# le_grand_strum_stencil.net
KiCad netlist of a schematic drawn in EAGLE
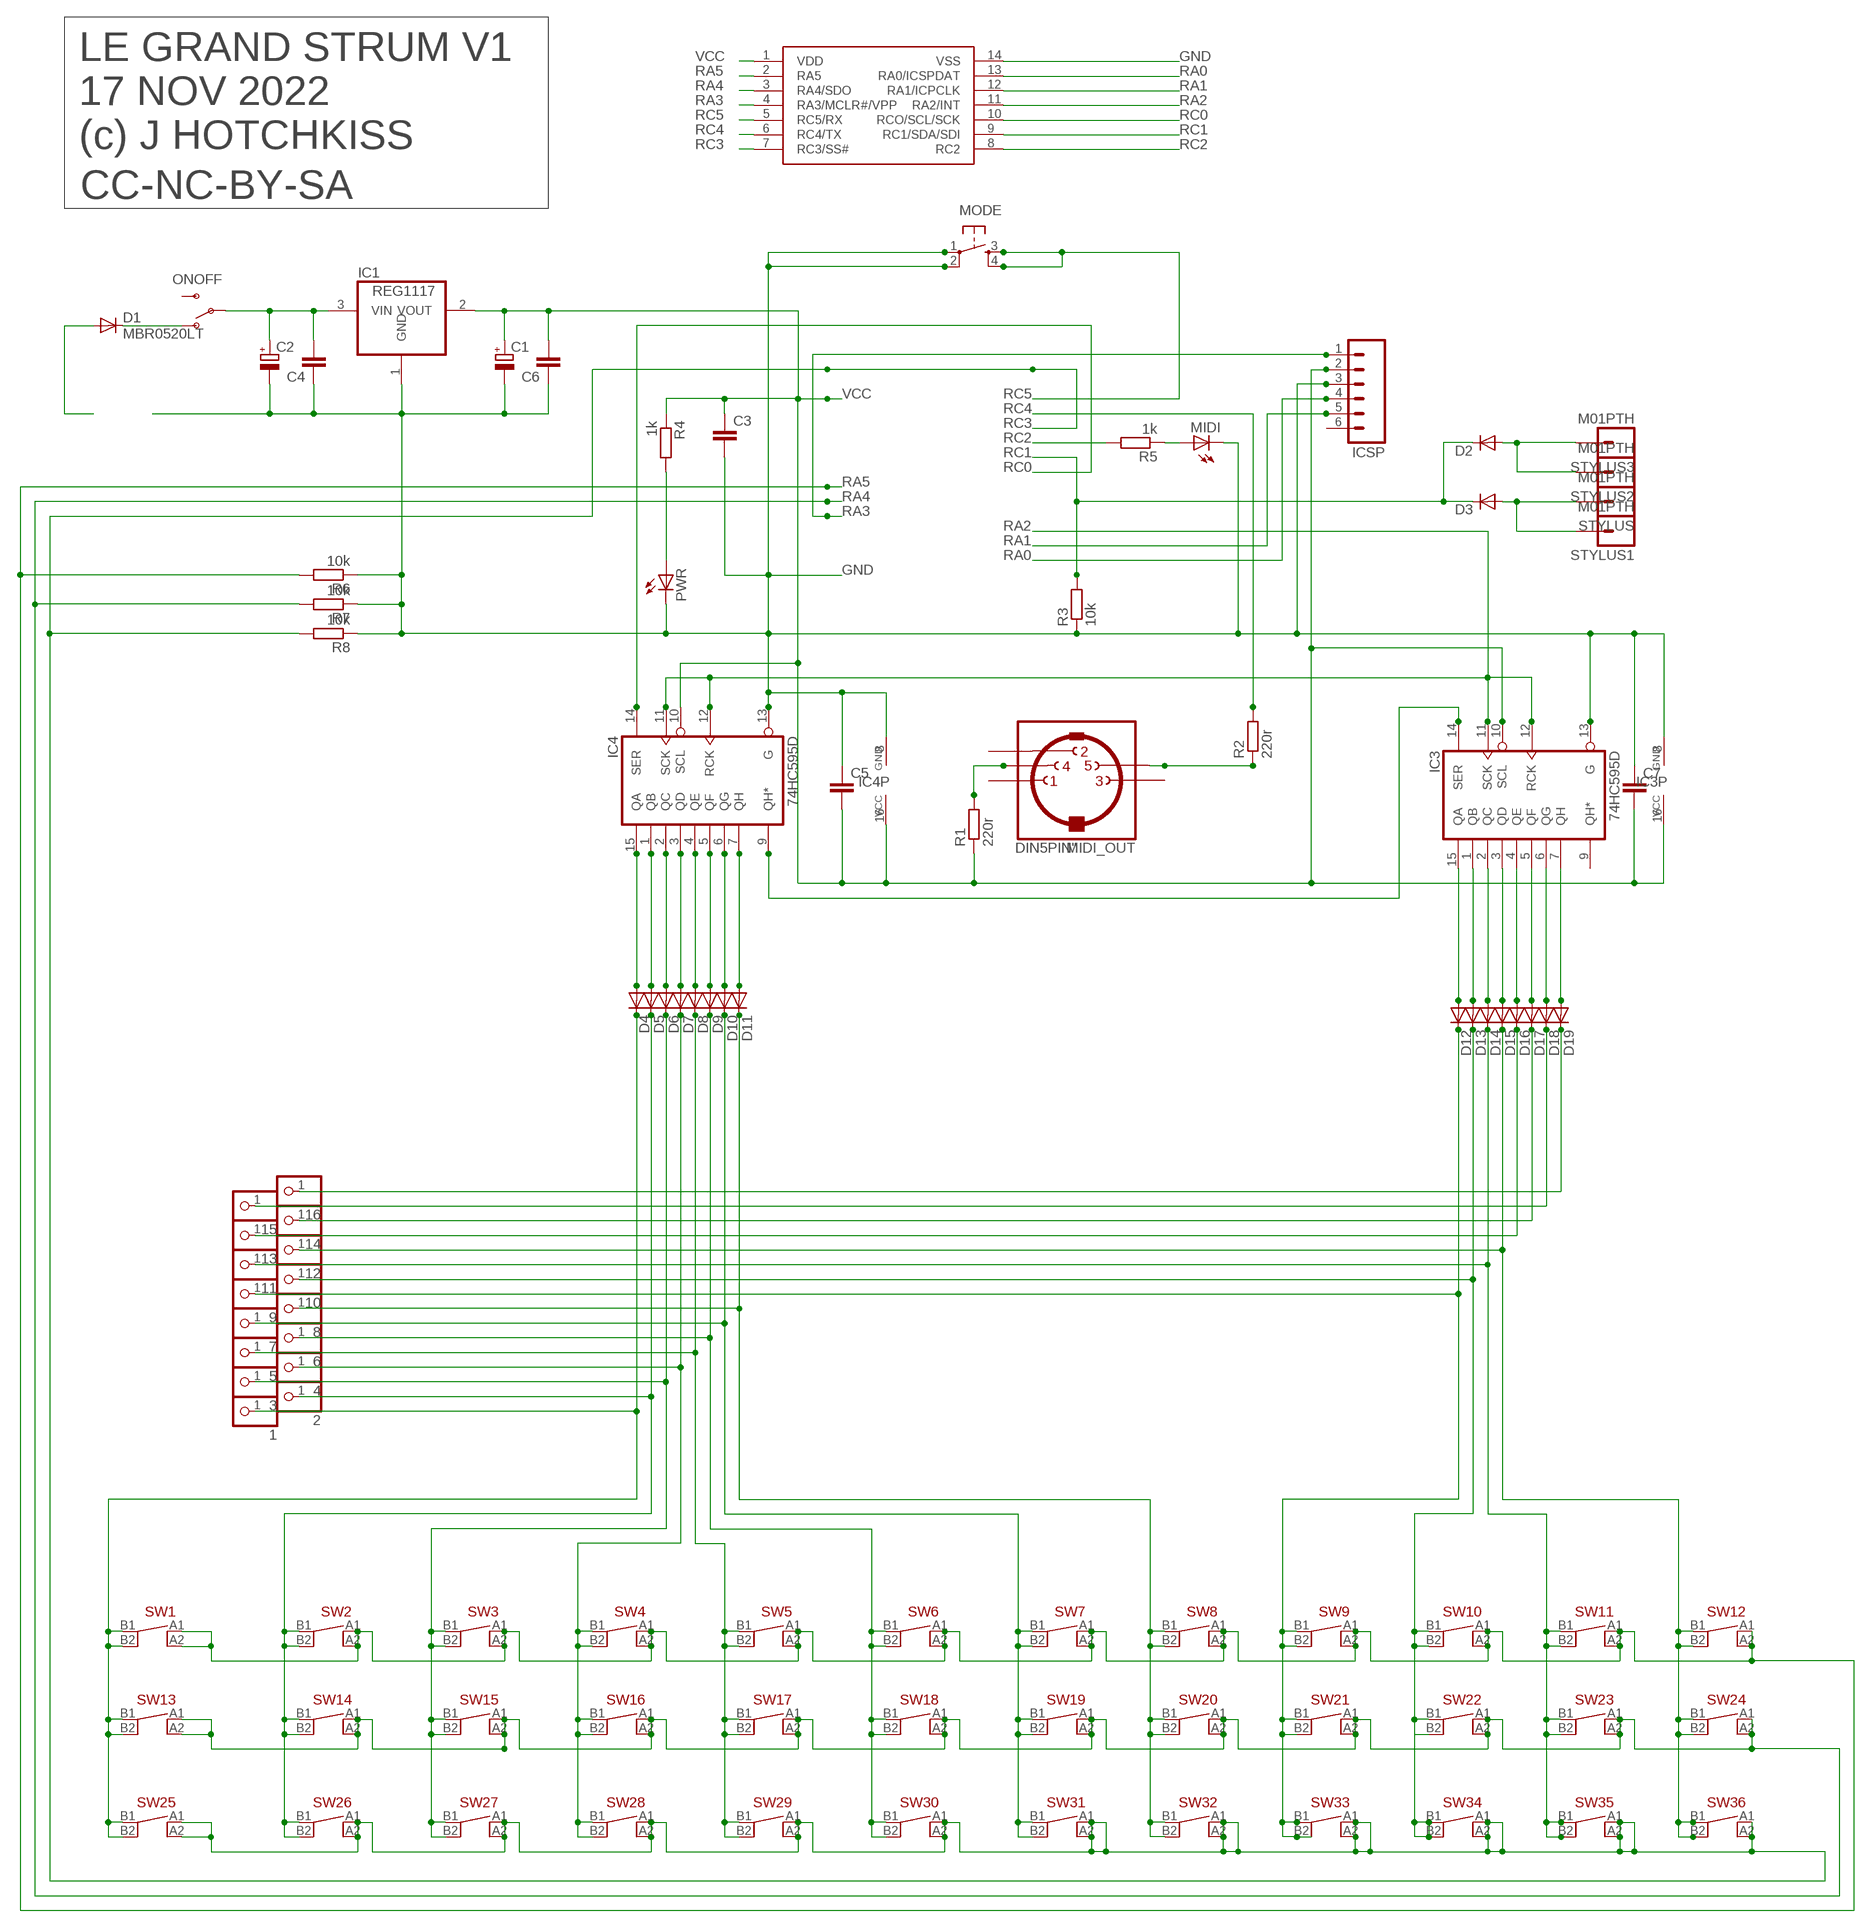
[diagram p0: schematic, sheet 1]

(export (version "E")
  (design (tool "Eeschema 10.0.6"))
  (components
    (comp (ref "1")
      (value "PINHD-1X1")
      (footprint "eagle-import:1X01")
      (libsource (lib "eagle-import") (part "PINHD-1X1"))
    )
    (comp (ref "2")
      (value "PINHD-1X1")
      (footprint "eagle-import:1X01")
      (libsource (lib "eagle-import") (part "PINHD-1X1"))
    )
    (comp (ref "3")
      (value "PINHD-1X1")
      (footprint "eagle-import:1X01")
      (libsource (lib "eagle-import") (part "PINHD-1X1"))
    )
    (comp (ref "4")
      (value "PINHD-1X1")
      (footprint "eagle-import:1X01")
      (libsource (lib "eagle-import") (part "PINHD-1X1"))
    )
    (comp (ref "5")
      (value "PINHD-1X1")
      (footprint "eagle-import:1X01")
      (libsource (lib "eagle-import") (part "PINHD-1X1"))
    )
    (comp (ref "6")
      (value "PINHD-1X1")
      (footprint "eagle-import:1X01")
      (libsource (lib "eagle-import") (part "PINHD-1X1"))
    )
    (comp (ref "7")
      (value "PINHD-1X1")
      (footprint "eagle-import:1X01")
      (libsource (lib "eagle-import") (part "PINHD-1X1"))
    )
    (comp (ref "8")
      (value "PINHD-1X1")
      (footprint "eagle-import:1X01")
      (libsource (lib "eagle-import") (part "PINHD-1X1"))
    )
    (comp (ref "9")
      (value "PINHD-1X1")
      (footprint "eagle-import:1X01")
      (libsource (lib "eagle-import") (part "PINHD-1X1"))
    )
    (comp (ref "10")
      (value "PINHD-1X1")
      (footprint "eagle-import:1X01")
      (libsource (lib "eagle-import") (part "PINHD-1X1"))
    )
    (comp (ref "11")
      (value "PINHD-1X1")
      (footprint "eagle-import:1X01")
      (libsource (lib "eagle-import") (part "PINHD-1X1"))
    )
    (comp (ref "12")
      (value "PINHD-1X1")
      (footprint "eagle-import:1X01")
      (libsource (lib "eagle-import") (part "PINHD-1X1"))
    )
    (comp (ref "13")
      (value "PINHD-1X1")
      (footprint "eagle-import:1X01")
      (libsource (lib "eagle-import") (part "PINHD-1X1"))
    )
    (comp (ref "14")
      (value "PINHD-1X1")
      (footprint "eagle-import:1X01")
      (libsource (lib "eagle-import") (part "PINHD-1X1"))
    )
    (comp (ref "15")
      (value "PINHD-1X1")
      (footprint "eagle-import:1X01")
      (libsource (lib "eagle-import") (part "PINHD-1X1"))
    )
    (comp (ref "16")
      (value "PINHD-1X1")
      (footprint "eagle-import:1X01")
      (libsource (lib "eagle-import") (part "PINHD-1X1"))
    )
    (comp (ref "C1")
      (value "CPOL-EUE2-5")
      (footprint "eagle-import:E2-5")
      (libsource (lib "eagle-import") (part "CPOL-EUE2-5"))
    )
    (comp (ref "C2")
      (value "CPOL-EUE2-5")
      (footprint "eagle-import:E2-5")
      (libsource (lib "eagle-import") (part "CPOL-EUE2-5"))
    )
    (comp (ref "C3")
      (value "C-EUC0805")
      (footprint "eagle-import:C0805")
      (libsource (lib "eagle-import") (part "C-EUC0805"))
    )
    (comp (ref "C4")
      (value "C-EUC0805")
      (footprint "eagle-import:C0805")
      (libsource (lib "eagle-import") (part "C-EUC0805"))
    )
    (comp (ref "C5")
      (value "C-EUC0805")
      (footprint "eagle-import:C0805")
      (libsource (lib "eagle-import") (part "C-EUC0805"))
    )
    (comp (ref "C6")
      (value "C-EUC0805")
      (footprint "eagle-import:C0805")
      (libsource (lib "eagle-import") (part "C-EUC0805"))
    )
    (comp (ref "C7")
      (value "C-EUC0805")
      (footprint "eagle-import:C0805")
      (libsource (lib "eagle-import") (part "C-EUC0805"))
    )
    (comp (ref "D1")
      (value "MBR0520LT")
      (footprint "eagle-import:SOD123")
      (libsource (lib "eagle-import") (part "MBR0520LT"))
    )
    (comp (ref "D2")
      (value "TS4148")
      (footprint "eagle-import:D0805")
      (libsource (lib "eagle-import") (part "TS4148"))
    )
    (comp (ref "D3")
      (value "TS4148")
      (footprint "eagle-import:D0805")
      (libsource (lib "eagle-import") (part "TS4148"))
    )
    (comp (ref "D4")
      (value "TS4148")
      (footprint "eagle-import:D0805")
      (libsource (lib "eagle-import") (part "TS4148"))
    )
    (comp (ref "D5")
      (value "TS4148")
      (footprint "eagle-import:D0805")
      (libsource (lib "eagle-import") (part "TS4148"))
    )
    (comp (ref "D6")
      (value "TS4148")
      (footprint "eagle-import:D0805")
      (libsource (lib "eagle-import") (part "TS4148"))
    )
    (comp (ref "D7")
      (value "TS4148")
      (footprint "eagle-import:D0805")
      (libsource (lib "eagle-import") (part "TS4148"))
    )
    (comp (ref "D8")
      (value "TS4148")
      (footprint "eagle-import:D0805")
      (libsource (lib "eagle-import") (part "TS4148"))
    )
    (comp (ref "D9")
      (value "TS4148")
      (footprint "eagle-import:D0805")
      (libsource (lib "eagle-import") (part "TS4148"))
    )
    (comp (ref "D10")
      (value "TS4148")
      (footprint "eagle-import:D0805")
      (libsource (lib "eagle-import") (part "TS4148"))
    )
    (comp (ref "D11")
      (value "TS4148")
      (footprint "eagle-import:D0805")
      (libsource (lib "eagle-import") (part "TS4148"))
    )
    (comp (ref "D12")
      (value "TS4148")
      (footprint "eagle-import:D0805")
      (libsource (lib "eagle-import") (part "TS4148"))
    )
    (comp (ref "D13")
      (value "TS4148")
      (footprint "eagle-import:D0805")
      (libsource (lib "eagle-import") (part "TS4148"))
    )
    (comp (ref "D14")
      (value "TS4148")
      (footprint "eagle-import:D0805")
      (libsource (lib "eagle-import") (part "TS4148"))
    )
    (comp (ref "D15")
      (value "TS4148")
      (footprint "eagle-import:D0805")
      (libsource (lib "eagle-import") (part "TS4148"))
    )
    (comp (ref "D16")
      (value "TS4148")
      (footprint "eagle-import:D0805")
      (libsource (lib "eagle-import") (part "TS4148"))
    )
    (comp (ref "D17")
      (value "TS4148")
      (footprint "eagle-import:D0805")
      (libsource (lib "eagle-import") (part "TS4148"))
    )
    (comp (ref "D18")
      (value "TS4148")
      (footprint "eagle-import:D0805")
      (libsource (lib "eagle-import") (part "TS4148"))
    )
    (comp (ref "D19")
      (value "TS4148")
      (footprint "eagle-import:D0805")
      (libsource (lib "eagle-import") (part "TS4148"))
    )
    (comp (ref "IC1")
      (value "REG1117")
      (footprint "eagle-import:SOT223")
      (libsource (lib "eagle-import") (part "REG1117"))
    )
    (comp (ref "IC2")
      (value "PIC16F1825SO14")
      (footprint "eagle-import:SO14")
      (libsource (lib "eagle-import") (part "PIC16F1825SO14"))
    )
    (comp (ref "IC3")
      (value "74HC595D")
      (footprint "eagle-import:SO16")
      (libsource (lib "eagle-import") (part "74595DHC"))
    )
    (comp (ref "IC4")
      (value "74HC595D")
      (footprint "eagle-import:SO16")
      (libsource (lib "eagle-import") (part "74595DHC"))
    )
    (comp (ref "ICSP")
      (value "M06SIP")
      (footprint "eagle-import:1X06")
      (libsource (lib "eagle-import") (part "M06SIP"))
    )
    (comp (ref "MIDI")
      (value "LEDCHIPLED_0805")
      (footprint "eagle-import:CHIPLED_0805")
      (libsource (lib "eagle-import") (part "LEDCHIPLED_0805"))
    )
    (comp (ref "MIDI_OUT")
      (value "DIN5PIN\"")
      (footprint "eagle-import:TRUCONN90")
      (libsource (lib "eagle-import") (part "DIN5PIN{dblquote}"))
    )
    (comp (ref "MODE")
      (value "TAC_SWITCHPTH")
      (footprint "eagle-import:TACTILE-PTH")
      (libsource (lib "eagle-import") (part "TAC_SWITCHPTH"))
    )
    (comp (ref "ONOFF")
      (value "SWITCH-SPSTPTH")
      (footprint "eagle-import:SWITCH-SPDT")
      (libsource (lib "eagle-import") (part "SWITCH-SPSTPTH"))
    )
    (comp (ref "PWR")
      (value "LEDCHIPLED_0805")
      (footprint "eagle-import:CHIPLED_0805")
      (libsource (lib "eagle-import") (part "LEDCHIPLED_0805"))
    )
    (comp (ref "R1")
      (value "220r")
      (footprint "eagle-import:R0805")
      (libsource (lib "eagle-import") (part "R-EU_R0805"))
    )
    (comp (ref "R2")
      (value "220r")
      (footprint "eagle-import:R0805")
      (libsource (lib "eagle-import") (part "R-EU_R0805"))
    )
    (comp (ref "R3")
      (value "10k")
      (footprint "eagle-import:R0805")
      (libsource (lib "eagle-import") (part "R-EU_R0805"))
    )
    (comp (ref "R4")
      (value "1k")
      (footprint "eagle-import:R0805")
      (libsource (lib "eagle-import") (part "R-EU_R0805"))
    )
    (comp (ref "R5")
      (value "1k")
      (footprint "eagle-import:R0805")
      (libsource (lib "eagle-import") (part "R-EU_R0805"))
    )
    (comp (ref "R6")
      (value "10k")
      (footprint "eagle-import:R0805")
      (libsource (lib "eagle-import") (part "R-EU_R0805"))
    )
    (comp (ref "R7")
      (value "10k")
      (footprint "eagle-import:R0805")
      (libsource (lib "eagle-import") (part "R-EU_R0805"))
    )
    (comp (ref "R8")
      (value "10k")
      (footprint "eagle-import:R0805")
      (libsource (lib "eagle-import") (part "R-EU_R0805"))
    )
    (comp (ref "STYLUS")
      (value "M01PTH")
      (footprint "eagle-import:1X01")
      (libsource (lib "eagle-import") (part "M01PTH"))
    )
    (comp (ref "STYLUS1")
      (value "M01PTH")
      (footprint "eagle-import:1X01")
      (libsource (lib "eagle-import") (part "M01PTH"))
    )
    (comp (ref "STYLUS2")
      (value "M01PTH")
      (footprint "eagle-import:1X01")
      (libsource (lib "eagle-import") (part "M01PTH"))
    )
    (comp (ref "STYLUS3")
      (value "M01PTH")
      (footprint "eagle-import:1X01")
      (libsource (lib "eagle-import") (part "M01PTH"))
    )
    (comp (ref "SW1")
      (value "12MMTACT_SMT")
      (footprint "eagle-import:12MMTACT_SMT")
      (libsource (lib "eagle-import") (part "12MMTACT_SMT"))
    )
    (comp (ref "SW2")
      (value "12MMTACT_SMT")
      (footprint "eagle-import:12MMTACT_SMT")
      (libsource (lib "eagle-import") (part "12MMTACT_SMT"))
    )
    (comp (ref "SW3")
      (value "12MMTACT_SMT")
      (footprint "eagle-import:12MMTACT_SMT")
      (libsource (lib "eagle-import") (part "12MMTACT_SMT"))
    )
    (comp (ref "SW4")
      (value "12MMTACT_SMT")
      (footprint "eagle-import:12MMTACT_SMT")
      (libsource (lib "eagle-import") (part "12MMTACT_SMT"))
    )
    (comp (ref "SW5")
      (value "12MMTACT_SMT")
      (footprint "eagle-import:12MMTACT_SMT")
      (libsource (lib "eagle-import") (part "12MMTACT_SMT"))
    )
    (comp (ref "SW6")
      (value "12MMTACT_SMT")
      (footprint "eagle-import:12MMTACT_SMT")
      (libsource (lib "eagle-import") (part "12MMTACT_SMT"))
    )
    (comp (ref "SW7")
      (value "12MMTACT_SMT")
      (footprint "eagle-import:12MMTACT_SMT")
      (libsource (lib "eagle-import") (part "12MMTACT_SMT"))
    )
    (comp (ref "SW8")
      (value "12MMTACT_SMT")
      (footprint "eagle-import:12MMTACT_SMT")
      (libsource (lib "eagle-import") (part "12MMTACT_SMT"))
    )
    (comp (ref "SW9")
      (value "12MMTACT_SMT")
      (footprint "eagle-import:12MMTACT_SMT")
      (libsource (lib "eagle-import") (part "12MMTACT_SMT"))
    )
    (comp (ref "SW10")
      (value "12MMTACT_SMT")
      (footprint "eagle-import:12MMTACT_SMT")
      (libsource (lib "eagle-import") (part "12MMTACT_SMT"))
    )
    (comp (ref "SW11")
      (value "12MMTACT_SMT")
      (footprint "eagle-import:12MMTACT_SMT")
      (libsource (lib "eagle-import") (part "12MMTACT_SMT"))
    )
    (comp (ref "SW12")
      (value "12MMTACT_SMT")
      (footprint "eagle-import:12MMTACT_SMT")
      (libsource (lib "eagle-import") (part "12MMTACT_SMT"))
    )
    (comp (ref "SW13")
      (value "12MMTACT_SMT")
      (footprint "eagle-import:12MMTACT_SMT")
      (libsource (lib "eagle-import") (part "12MMTACT_SMT"))
    )
    (comp (ref "SW14")
      (value "12MMTACT_SMT")
      (footprint "eagle-import:12MMTACT_SMT")
      (libsource (lib "eagle-import") (part "12MMTACT_SMT"))
    )
    (comp (ref "SW15")
      (value "12MMTACT_SMT")
      (footprint "eagle-import:12MMTACT_SMT")
      (libsource (lib "eagle-import") (part "12MMTACT_SMT"))
    )
    (comp (ref "SW16")
      (value "12MMTACT_SMT")
      (footprint "eagle-import:12MMTACT_SMT")
      (libsource (lib "eagle-import") (part "12MMTACT_SMT"))
    )
    (comp (ref "SW17")
      (value "12MMTACT_SMT")
      (footprint "eagle-import:12MMTACT_SMT")
      (libsource (lib "eagle-import") (part "12MMTACT_SMT"))
    )
    (comp (ref "SW18")
      (value "12MMTACT_SMT")
      (footprint "eagle-import:12MMTACT_SMT")
      (libsource (lib "eagle-import") (part "12MMTACT_SMT"))
    )
    (comp (ref "SW19")
      (value "12MMTACT_SMT")
      (footprint "eagle-import:12MMTACT_SMT")
      (libsource (lib "eagle-import") (part "12MMTACT_SMT"))
    )
    (comp (ref "SW20")
      (value "12MMTACT_SMT")
      (footprint "eagle-import:12MMTACT_SMT")
      (libsource (lib "eagle-import") (part "12MMTACT_SMT"))
    )
    (comp (ref "SW21")
      (value "12MMTACT_SMT")
      (footprint "eagle-import:12MMTACT_SMT")
      (libsource (lib "eagle-import") (part "12MMTACT_SMT"))
    )
    (comp (ref "SW22")
      (value "12MMTACT_SMT")
      (footprint "eagle-import:12MMTACT_SMT")
      (libsource (lib "eagle-import") (part "12MMTACT_SMT"))
    )
    (comp (ref "SW23")
      (value "12MMTACT_SMT")
      (footprint "eagle-import:12MMTACT_SMT")
      (libsource (lib "eagle-import") (part "12MMTACT_SMT"))
    )
    (comp (ref "SW24")
      (value "12MMTACT_SMT")
      (footprint "eagle-import:12MMTACT_SMT")
      (libsource (lib "eagle-import") (part "12MMTACT_SMT"))
    )
    (comp (ref "SW25")
      (value "12MMTACT_SMT")
      (footprint "eagle-import:12MMTACT_SMT")
      (libsource (lib "eagle-import") (part "12MMTACT_SMT"))
    )
    (comp (ref "SW26")
      (value "12MMTACT_SMT")
      (footprint "eagle-import:12MMTACT_SMT")
      (libsource (lib "eagle-import") (part "12MMTACT_SMT"))
    )
    (comp (ref "SW27")
      (value "12MMTACT_SMT")
      (footprint "eagle-import:12MMTACT_SMT")
      (libsource (lib "eagle-import") (part "12MMTACT_SMT"))
    )
    (comp (ref "SW28")
      (value "12MMTACT_SMT")
      (footprint "eagle-import:12MMTACT_SMT")
      (libsource (lib "eagle-import") (part "12MMTACT_SMT"))
    )
    (comp (ref "SW29")
      (value "12MMTACT_SMT")
      (footprint "eagle-import:12MMTACT_SMT")
      (libsource (lib "eagle-import") (part "12MMTACT_SMT"))
    )
    (comp (ref "SW30")
      (value "12MMTACT_SMT")
      (footprint "eagle-import:12MMTACT_SMT")
      (libsource (lib "eagle-import") (part "12MMTACT_SMT"))
    )
    (comp (ref "SW31")
      (value "12MMTACT_SMT")
      (footprint "eagle-import:12MMTACT_SMT")
      (libsource (lib "eagle-import") (part "12MMTACT_SMT"))
    )
    (comp (ref "SW32")
      (value "12MMTACT_SMT")
      (footprint "eagle-import:12MMTACT_SMT")
      (libsource (lib "eagle-import") (part "12MMTACT_SMT"))
    )
    (comp (ref "SW33")
      (value "12MMTACT_SMT")
      (footprint "eagle-import:12MMTACT_SMT")
      (libsource (lib "eagle-import") (part "12MMTACT_SMT"))
    )
    (comp (ref "SW34")
      (value "12MMTACT_SMT")
      (footprint "eagle-import:12MMTACT_SMT")
      (libsource (lib "eagle-import") (part "12MMTACT_SMT"))
    )
    (comp (ref "SW35")
      (value "12MMTACT_SMT")
      (footprint "eagle-import:12MMTACT_SMT")
      (libsource (lib "eagle-import") (part "12MMTACT_SMT"))
    )
    (comp (ref "SW36")
      (value "12MMTACT_SMT")
      (footprint "eagle-import:12MMTACT_SMT")
      (libsource (lib "eagle-import") (part "12MMTACT_SMT"))
    )
  )
  (nets
    (net (code "1") (name "/GND") (class "Default")
      (node (ref "C1") (pin "-") (pinfunction "-_-") (pintype "passive"))
      (node (ref "C2") (pin "-") (pinfunction "-_-") (pintype "passive"))
      (node (ref "C3") (pin "2") (pinfunction "2_2") (pintype "passive"))
      (node (ref "C4") (pin "1") (pinfunction "1_1") (pintype "passive"))
      (node (ref "C5") (pin "1") (pinfunction "1_1") (pintype "passive"))
      (node (ref "C6") (pin "1") (pinfunction "1_1") (pintype "passive"))
      (node (ref "C7") (pin "1") (pinfunction "1_1") (pintype "passive"))
      (node (ref "IC1") (pin "1") (pinfunction "GND_1") (pintype "power_in"))
      (node (ref "IC2") (pin "14") (pinfunction "VSS_14") (pintype "power_in"))
      (node (ref "IC3") (pin "13") (pinfunction "G_13") (pintype "input"))
      (node (ref "IC3") (pin "8") (pinfunction "GND_8") (pintype "power_in"))
      (node (ref "IC4") (pin "13") (pinfunction "G_13") (pintype "input"))
      (node (ref "IC4") (pin "8") (pinfunction "GND_8") (pintype "power_in"))
      (node (ref "ICSP") (pin "3") (pinfunction "3_3") (pintype "passive"))
      (node (ref "MIDI") (pin "C") (pinfunction "C_C") (pintype "passive"))
      (node (ref "MODE") (pin "1") (pinfunction "1_1") (pintype "passive"))
      (node (ref "MODE") (pin "2") (pinfunction "2_2") (pintype "passive"))
      (node (ref "PWR") (pin "C") (pinfunction "C_C") (pintype "passive"))
      (node (ref "R3") (pin "1") (pinfunction "1_1") (pintype "passive"))
      (node (ref "R6") (pin "1") (pinfunction "1_1") (pintype "passive"))
      (node (ref "R7") (pin "1") (pinfunction "1_1") (pintype "passive"))
      (node (ref "R8") (pin "1") (pinfunction "1_1") (pintype "passive"))
    )
    (net (code "2") (name "/RA0") (class "Default")
      (node (ref "IC2") (pin "13") (pinfunction "RA0/ICSPDAT_13") (pintype "bidirectional"))
      (node (ref "ICSP") (pin "4") (pinfunction "4_4") (pintype "passive"))
    )
    (net (code "3") (name "/RA1") (class "Default")
      (node (ref "IC2") (pin "12") (pinfunction "RA1/ICPCLK_12") (pintype "bidirectional"))
      (node (ref "ICSP") (pin "5") (pinfunction "5_5") (pintype "passive"))
    )
    (net (code "4") (name "/RA2") (class "Default")
      (node (ref "IC2") (pin "11") (pinfunction "RA2/INT_11") (pintype "bidirectional"))
      (node (ref "IC3") (pin "11") (pinfunction "SCK_11") (pintype "input"))
      (node (ref "IC3") (pin "12") (pinfunction "RCK_12") (pintype "input"))
      (node (ref "IC4") (pin "11") (pinfunction "SCK_11") (pintype "input"))
      (node (ref "IC4") (pin "12") (pinfunction "RCK_12") (pintype "input"))
    )
    (net (code "5") (name "/RA3") (class "Default")
      (node (ref "IC2") (pin "4") (pinfunction "RA3/MCLR#/VPP_4") (pintype "input"))
      (node (ref "ICSP") (pin "1") (pinfunction "1_1") (pintype "passive"))
    )
    (net (code "6") (name "/RA4") (class "Default")
      (node (ref "IC2") (pin "3") (pinfunction "RA4/SDO_3") (pintype "bidirectional"))
      (node (ref "R7") (pin "2") (pinfunction "2_2") (pintype "passive"))
      (node (ref "SW13") (pin "A1") (pinfunction "1_A1") (pintype "bidirectional"))
      (node (ref "SW13") (pin "A2") (pinfunction "2_A2") (pintype "bidirectional"))
      (node (ref "SW14") (pin "A1") (pinfunction "1_A1") (pintype "bidirectional"))
      (node (ref "SW14") (pin "A2") (pinfunction "2_A2") (pintype "bidirectional"))
      (node (ref "SW15") (pin "A1") (pinfunction "1_A1") (pintype "bidirectional"))
      (node (ref "SW15") (pin "A2") (pinfunction "2_A2") (pintype "bidirectional"))
      (node (ref "SW16") (pin "A1") (pinfunction "1_A1") (pintype "bidirectional"))
      (node (ref "SW16") (pin "A2") (pinfunction "2_A2") (pintype "bidirectional"))
      (node (ref "SW17") (pin "A1") (pinfunction "1_A1") (pintype "bidirectional"))
      (node (ref "SW17") (pin "A2") (pinfunction "2_A2") (pintype "bidirectional"))
      (node (ref "SW18") (pin "A1") (pinfunction "1_A1") (pintype "bidirectional"))
      (node (ref "SW18") (pin "A2") (pinfunction "2_A2") (pintype "bidirectional"))
      (node (ref "SW19") (pin "A1") (pinfunction "1_A1") (pintype "bidirectional"))
      (node (ref "SW19") (pin "A2") (pinfunction "2_A2") (pintype "bidirectional"))
      (node (ref "SW20") (pin "A1") (pinfunction "1_A1") (pintype "bidirectional"))
      (node (ref "SW20") (pin "A2") (pinfunction "2_A2") (pintype "bidirectional"))
      (node (ref "SW21") (pin "A1") (pinfunction "1_A1") (pintype "bidirectional"))
      (node (ref "SW21") (pin "A2") (pinfunction "2_A2") (pintype "bidirectional"))
      (node (ref "SW22") (pin "A1") (pinfunction "1_A1") (pintype "bidirectional"))
      (node (ref "SW22") (pin "A2") (pinfunction "2_A2") (pintype "bidirectional"))
      (node (ref "SW23") (pin "A1") (pinfunction "1_A1") (pintype "bidirectional"))
      (node (ref "SW23") (pin "A2") (pinfunction "2_A2") (pintype "bidirectional"))
      (node (ref "SW24") (pin "A1") (pinfunction "1_A1") (pintype "bidirectional"))
      (node (ref "SW24") (pin "A2") (pinfunction "2_A2") (pintype "bidirectional"))
    )
    (net (code "7") (name "/RA5") (class "Default")
      (node (ref "IC2") (pin "2") (pinfunction "RA5_2") (pintype "bidirectional"))
      (node (ref "R6") (pin "2") (pinfunction "2_2") (pintype "passive"))
      (node (ref "SW1") (pin "A1") (pinfunction "1_A1") (pintype "bidirectional"))
      (node (ref "SW1") (pin "A2") (pinfunction "2_A2") (pintype "bidirectional"))
      (node (ref "SW10") (pin "A1") (pinfunction "1_A1") (pintype "bidirectional"))
      (node (ref "SW10") (pin "A2") (pinfunction "2_A2") (pintype "bidirectional"))
      (node (ref "SW11") (pin "A1") (pinfunction "1_A1") (pintype "bidirectional"))
      (node (ref "SW11") (pin "A2") (pinfunction "2_A2") (pintype "bidirectional"))
      (node (ref "SW12") (pin "A1") (pinfunction "1_A1") (pintype "bidirectional"))
      (node (ref "SW12") (pin "A2") (pinfunction "2_A2") (pintype "bidirectional"))
      (node (ref "SW2") (pin "A1") (pinfunction "1_A1") (pintype "bidirectional"))
      (node (ref "SW2") (pin "A2") (pinfunction "2_A2") (pintype "bidirectional"))
      (node (ref "SW3") (pin "A1") (pinfunction "1_A1") (pintype "bidirectional"))
      (node (ref "SW3") (pin "A2") (pinfunction "2_A2") (pintype "bidirectional"))
      (node (ref "SW4") (pin "A1") (pinfunction "1_A1") (pintype "bidirectional"))
      (node (ref "SW4") (pin "A2") (pinfunction "2_A2") (pintype "bidirectional"))
      (node (ref "SW5") (pin "A1") (pinfunction "1_A1") (pintype "bidirectional"))
      (node (ref "SW5") (pin "A2") (pinfunction "2_A2") (pintype "bidirectional"))
      (node (ref "SW6") (pin "A1") (pinfunction "1_A1") (pintype "bidirectional"))
      (node (ref "SW6") (pin "A2") (pinfunction "2_A2") (pintype "bidirectional"))
      (node (ref "SW7") (pin "A1") (pinfunction "1_A1") (pintype "bidirectional"))
      (node (ref "SW7") (pin "A2") (pinfunction "2_A2") (pintype "bidirectional"))
      (node (ref "SW8") (pin "A1") (pinfunction "1_A1") (pintype "bidirectional"))
      (node (ref "SW8") (pin "A2") (pinfunction "2_A2") (pintype "bidirectional"))
      (node (ref "SW9") (pin "A1") (pinfunction "1_A1") (pintype "bidirectional"))
      (node (ref "SW9") (pin "A2") (pinfunction "2_A2") (pintype "bidirectional"))
    )
    (net (code "8") (name "/RC0") (class "Default")
      (node (ref "IC2") (pin "10") (pinfunction "RCO/SCL/SCK_10") (pintype "bidirectional"))
      (node (ref "IC4") (pin "14") (pinfunction "SER_14") (pintype "input"))
    )
    (net (code "9") (name "/RC1") (class "Default")
      (node (ref "D2") (pin "K") (pinfunction "C_K") (pintype "passive"))
      (node (ref "D3") (pin "K") (pinfunction "C_K") (pintype "passive"))
      (node (ref "IC2") (pin "9") (pinfunction "RC1/SDA/SDI_9") (pintype "bidirectional"))
      (node (ref "R3") (pin "2") (pinfunction "2_2") (pintype "passive"))
    )
    (net (code "10") (name "/RC2") (class "Default")
      (node (ref "IC2") (pin "8") (pinfunction "RC2_8") (pintype "bidirectional"))
      (node (ref "R5") (pin "2") (pinfunction "2_2") (pintype "passive"))
    )
    (net (code "11") (name "/RC3") (class "Default")
      (node (ref "IC2") (pin "7") (pinfunction "RC3/SS#_7") (pintype "bidirectional"))
      (node (ref "R8") (pin "2") (pinfunction "2_2") (pintype "passive"))
      (node (ref "SW25") (pin "A1") (pinfunction "1_A1") (pintype "bidirectional"))
      (node (ref "SW25") (pin "A2") (pinfunction "2_A2") (pintype "bidirectional"))
      (node (ref "SW26") (pin "A1") (pinfunction "1_A1") (pintype "bidirectional"))
      (node (ref "SW26") (pin "A2") (pinfunction "2_A2") (pintype "bidirectional"))
      (node (ref "SW27") (pin "A1") (pinfunction "1_A1") (pintype "bidirectional"))
      (node (ref "SW27") (pin "A2") (pinfunction "2_A2") (pintype "bidirectional"))
      (node (ref "SW28") (pin "A1") (pinfunction "1_A1") (pintype "bidirectional"))
      (node (ref "SW28") (pin "A2") (pinfunction "2_A2") (pintype "bidirectional"))
      (node (ref "SW29") (pin "A1") (pinfunction "1_A1") (pintype "bidirectional"))
      (node (ref "SW29") (pin "A2") (pinfunction "2_A2") (pintype "bidirectional"))
      (node (ref "SW30") (pin "A1") (pinfunction "1_A1") (pintype "bidirectional"))
      (node (ref "SW30") (pin "A2") (pinfunction "2_A2") (pintype "bidirectional"))
      (node (ref "SW31") (pin "A1") (pinfunction "1_A1") (pintype "bidirectional"))
      (node (ref "SW31") (pin "A2") (pinfunction "2_A2") (pintype "bidirectional"))
      (node (ref "SW32") (pin "A1") (pinfunction "1_A1") (pintype "bidirectional"))
      (node (ref "SW32") (pin "A2") (pinfunction "2_A2") (pintype "bidirectional"))
      (node (ref "SW33") (pin "A1") (pinfunction "1_A1") (pintype "bidirectional"))
      (node (ref "SW33") (pin "A2") (pinfunction "2_A2") (pintype "bidirectional"))
      (node (ref "SW34") (pin "A1") (pinfunction "1_A1") (pintype "bidirectional"))
      (node (ref "SW34") (pin "A2") (pinfunction "2_A2") (pintype "bidirectional"))
      (node (ref "SW35") (pin "A1") (pinfunction "1_A1") (pintype "bidirectional"))
      (node (ref "SW35") (pin "A2") (pinfunction "2_A2") (pintype "bidirectional"))
      (node (ref "SW36") (pin "A1") (pinfunction "1_A1") (pintype "bidirectional"))
      (node (ref "SW36") (pin "A2") (pinfunction "2_A2") (pintype "bidirectional"))
    )
    (net (code "12") (name "/RC4") (class "Default")
      (node (ref "IC2") (pin "6") (pinfunction "RC4/TX_6") (pintype "bidirectional"))
      (node (ref "R2") (pin "2") (pinfunction "2_2") (pintype "passive"))
    )
    (net (code "13") (name "/RC5") (class "Default")
      (node (ref "IC2") (pin "5") (pinfunction "RC5/RX_5") (pintype "bidirectional"))
      (node (ref "MODE") (pin "3") (pinfunction "3_3") (pintype "passive"))
      (node (ref "MODE") (pin "4") (pinfunction "4_4") (pintype "passive"))
    )
    (net (code "14") (name "/VCC") (class "Default")
      (node (ref "C1") (pin "+") (pinfunction "+_+") (pintype "passive"))
      (node (ref "C3") (pin "1") (pinfunction "1_1") (pintype "passive"))
      (node (ref "C5") (pin "2") (pinfunction "2_2") (pintype "passive"))
      (node (ref "C6") (pin "2") (pinfunction "2_2") (pintype "passive"))
      (node (ref "C7") (pin "2") (pinfunction "2_2") (pintype "passive"))
      (node (ref "IC1") (pin "2") (pinfunction "VOUT_2") (pintype "output"))
      (node (ref "IC2") (pin "1") (pinfunction "VDD_1") (pintype "power_in"))
      (node (ref "IC3") (pin "10") (pinfunction "SCL_10") (pintype "input"))
      (node (ref "IC3") (pin "16") (pinfunction "VCC_16") (pintype "power_in"))
      (node (ref "IC4") (pin "10") (pinfunction "SCL_10") (pintype "input"))
      (node (ref "IC4") (pin "16") (pinfunction "VCC_16") (pintype "power_in"))
      (node (ref "ICSP") (pin "2") (pinfunction "2_2") (pintype "passive"))
      (node (ref "R1") (pin "1") (pinfunction "1_1") (pintype "passive"))
      (node (ref "R4") (pin "1") (pinfunction "1_1") (pintype "passive"))
    )
    (net (code "15") (name "Net-(D2-PadA)") (class "Default")
      (node (ref "D2") (pin "A") (pinfunction "A_A") (pintype "passive"))
      (node (ref "STYLUS2") (pin "1") (pinfunction "1_1") (pintype "passive"))
      (node (ref "STYLUS3") (pin "1") (pinfunction "1_1") (pintype "passive"))
    )
    (net (code "16") (name "Net-(D3-PadA)") (class "Default")
      (node (ref "D3") (pin "A") (pinfunction "A_A") (pintype "passive"))
      (node (ref "STYLUS") (pin "1") (pinfunction "1_1") (pintype "passive"))
      (node (ref "STYLUS1") (pin "1") (pinfunction "1_1") (pintype "passive"))
    )
    (net (code "17") (name "Net-(D4-C)") (class "Default")
      (node (ref "1") (pin "1") (pinfunction "1_1") (pintype "passive"))
      (node (ref "D4") (pin "K") (pinfunction "C_K") (pintype "passive"))
      (node (ref "SW1") (pin "B1") (pinfunction "3_B1") (pintype "bidirectional"))
      (node (ref "SW1") (pin "B2") (pinfunction "4_B2") (pintype "bidirectional"))
      (node (ref "SW13") (pin "B1") (pinfunction "3_B1") (pintype "bidirectional"))
      (node (ref "SW13") (pin "B2") (pinfunction "4_B2") (pintype "bidirectional"))
      (node (ref "SW25") (pin "B1") (pinfunction "3_B1") (pintype "bidirectional"))
      (node (ref "SW25") (pin "B2") (pinfunction "4_B2") (pintype "bidirectional"))
    )
    (net (code "18") (name "Net-(D5-C)") (class "Default")
      (node (ref "2") (pin "1") (pinfunction "1_1") (pintype "passive"))
      (node (ref "D5") (pin "K") (pinfunction "C_K") (pintype "passive"))
      (node (ref "SW14") (pin "B1") (pinfunction "3_B1") (pintype "bidirectional"))
      (node (ref "SW14") (pin "B2") (pinfunction "4_B2") (pintype "bidirectional"))
      (node (ref "SW2") (pin "B1") (pinfunction "3_B1") (pintype "bidirectional"))
      (node (ref "SW2") (pin "B2") (pinfunction "4_B2") (pintype "bidirectional"))
      (node (ref "SW26") (pin "B1") (pinfunction "3_B1") (pintype "bidirectional"))
      (node (ref "SW26") (pin "B2") (pinfunction "4_B2") (pintype "bidirectional"))
    )
    (net (code "19") (name "Net-(D6-C)") (class "Default")
      (node (ref "3") (pin "1") (pinfunction "1_1") (pintype "passive"))
      (node (ref "D6") (pin "K") (pinfunction "C_K") (pintype "passive"))
      (node (ref "SW15") (pin "B1") (pinfunction "3_B1") (pintype "bidirectional"))
      (node (ref "SW15") (pin "B2") (pinfunction "4_B2") (pintype "bidirectional"))
      (node (ref "SW27") (pin "B1") (pinfunction "3_B1") (pintype "bidirectional"))
      (node (ref "SW27") (pin "B2") (pinfunction "4_B2") (pintype "bidirectional"))
      (node (ref "SW3") (pin "B1") (pinfunction "3_B1") (pintype "bidirectional"))
      (node (ref "SW3") (pin "B2") (pinfunction "4_B2") (pintype "bidirectional"))
    )
    (net (code "20") (name "Net-(D7-C)") (class "Default")
      (node (ref "4") (pin "1") (pinfunction "1_1") (pintype "passive"))
      (node (ref "D7") (pin "K") (pinfunction "C_K") (pintype "passive"))
      (node (ref "SW16") (pin "B1") (pinfunction "3_B1") (pintype "bidirectional"))
      (node (ref "SW16") (pin "B2") (pinfunction "4_B2") (pintype "bidirectional"))
      (node (ref "SW28") (pin "B1") (pinfunction "3_B1") (pintype "bidirectional"))
      (node (ref "SW28") (pin "B2") (pinfunction "4_B2") (pintype "bidirectional"))
      (node (ref "SW4") (pin "B1") (pinfunction "3_B1") (pintype "bidirectional"))
      (node (ref "SW4") (pin "B2") (pinfunction "4_B2") (pintype "bidirectional"))
    )
    (net (code "21") (name "Net-(D8-C)") (class "Default")
      (node (ref "5") (pin "1") (pinfunction "1_1") (pintype "passive"))
      (node (ref "D8") (pin "K") (pinfunction "C_K") (pintype "passive"))
      (node (ref "SW17") (pin "B1") (pinfunction "3_B1") (pintype "bidirectional"))
      (node (ref "SW17") (pin "B2") (pinfunction "4_B2") (pintype "bidirectional"))
      (node (ref "SW29") (pin "B1") (pinfunction "3_B1") (pintype "bidirectional"))
      (node (ref "SW29") (pin "B2") (pinfunction "4_B2") (pintype "bidirectional"))
      (node (ref "SW5") (pin "B1") (pinfunction "3_B1") (pintype "bidirectional"))
      (node (ref "SW5") (pin "B2") (pinfunction "4_B2") (pintype "bidirectional"))
    )
    (net (code "22") (name "Net-(D9-C)") (class "Default")
      (node (ref "6") (pin "1") (pinfunction "1_1") (pintype "passive"))
      (node (ref "D9") (pin "K") (pinfunction "C_K") (pintype "passive"))
      (node (ref "SW18") (pin "B1") (pinfunction "3_B1") (pintype "bidirectional"))
      (node (ref "SW18") (pin "B2") (pinfunction "4_B2") (pintype "bidirectional"))
      (node (ref "SW30") (pin "B1") (pinfunction "3_B1") (pintype "bidirectional"))
      (node (ref "SW30") (pin "B2") (pinfunction "4_B2") (pintype "bidirectional"))
      (node (ref "SW6") (pin "B1") (pinfunction "3_B1") (pintype "bidirectional"))
      (node (ref "SW6") (pin "B2") (pinfunction "4_B2") (pintype "bidirectional"))
    )
    (net (code "23") (name "Net-(D10-C)") (class "Default")
      (node (ref "7") (pin "1") (pinfunction "1_1") (pintype "passive"))
      (node (ref "D10") (pin "K") (pinfunction "C_K") (pintype "passive"))
      (node (ref "SW19") (pin "B1") (pinfunction "3_B1") (pintype "bidirectional"))
      (node (ref "SW19") (pin "B2") (pinfunction "4_B2") (pintype "bidirectional"))
      (node (ref "SW31") (pin "B1") (pinfunction "3_B1") (pintype "bidirectional"))
      (node (ref "SW31") (pin "B2") (pinfunction "4_B2") (pintype "bidirectional"))
      (node (ref "SW7") (pin "B1") (pinfunction "3_B1") (pintype "bidirectional"))
      (node (ref "SW7") (pin "B2") (pinfunction "4_B2") (pintype "bidirectional"))
    )
    (net (code "24") (name "Net-(D11-C)") (class "Default")
      (node (ref "8") (pin "1") (pinfunction "1_1") (pintype "passive"))
      (node (ref "D11") (pin "K") (pinfunction "C_K") (pintype "passive"))
      (node (ref "SW20") (pin "B1") (pinfunction "3_B1") (pintype "bidirectional"))
      (node (ref "SW20") (pin "B2") (pinfunction "4_B2") (pintype "bidirectional"))
      (node (ref "SW32") (pin "B1") (pinfunction "3_B1") (pintype "bidirectional"))
      (node (ref "SW32") (pin "B2") (pinfunction "4_B2") (pintype "bidirectional"))
      (node (ref "SW8") (pin "B1") (pinfunction "3_B1") (pintype "bidirectional"))
      (node (ref "SW8") (pin "B2") (pinfunction "4_B2") (pintype "bidirectional"))
    )
    (net (code "25") (name "Net-(D12-C)") (class "Default")
      (node (ref "9") (pin "1") (pinfunction "1_1") (pintype "passive"))
      (node (ref "D12") (pin "K") (pinfunction "C_K") (pintype "passive"))
      (node (ref "SW21") (pin "B1") (pinfunction "3_B1") (pintype "bidirectional"))
      (node (ref "SW21") (pin "B2") (pinfunction "4_B2") (pintype "bidirectional"))
      (node (ref "SW33") (pin "B1") (pinfunction "3_B1") (pintype "bidirectional"))
      (node (ref "SW33") (pin "B2") (pinfunction "4_B2") (pintype "bidirectional"))
      (node (ref "SW9") (pin "B1") (pinfunction "3_B1") (pintype "bidirectional"))
      (node (ref "SW9") (pin "B2") (pinfunction "4_B2") (pintype "bidirectional"))
    )
    (net (code "26") (name "Net-(D13-C)") (class "Default")
      (node (ref "10") (pin "1") (pinfunction "1_1") (pintype "passive"))
      (node (ref "D13") (pin "K") (pinfunction "C_K") (pintype "passive"))
      (node (ref "SW10") (pin "B1") (pinfunction "3_B1") (pintype "bidirectional"))
      (node (ref "SW10") (pin "B2") (pinfunction "4_B2") (pintype "bidirectional"))
      (node (ref "SW22") (pin "B1") (pinfunction "3_B1") (pintype "bidirectional"))
      (node (ref "SW22") (pin "B2") (pinfunction "4_B2") (pintype "bidirectional"))
      (node (ref "SW34") (pin "B1") (pinfunction "3_B1") (pintype "bidirectional"))
      (node (ref "SW34") (pin "B2") (pinfunction "4_B2") (pintype "bidirectional"))
    )
    (net (code "27") (name "Net-(D14-C)") (class "Default")
      (node (ref "11") (pin "1") (pinfunction "1_1") (pintype "passive"))
      (node (ref "D14") (pin "K") (pinfunction "C_K") (pintype "passive"))
      (node (ref "SW11") (pin "B1") (pinfunction "3_B1") (pintype "bidirectional"))
      (node (ref "SW11") (pin "B2") (pinfunction "4_B2") (pintype "bidirectional"))
      (node (ref "SW23") (pin "B1") (pinfunction "3_B1") (pintype "bidirectional"))
      (node (ref "SW23") (pin "B2") (pinfunction "4_B2") (pintype "bidirectional"))
      (node (ref "SW35") (pin "B1") (pinfunction "3_B1") (pintype "bidirectional"))
      (node (ref "SW35") (pin "B2") (pinfunction "4_B2") (pintype "bidirectional"))
    )
    (net (code "28") (name "Net-(D15-C)") (class "Default")
      (node (ref "12") (pin "1") (pinfunction "1_1") (pintype "passive"))
      (node (ref "D15") (pin "K") (pinfunction "C_K") (pintype "passive"))
      (node (ref "SW12") (pin "B1") (pinfunction "3_B1") (pintype "bidirectional"))
      (node (ref "SW12") (pin "B2") (pinfunction "4_B2") (pintype "bidirectional"))
      (node (ref "SW24") (pin "B1") (pinfunction "3_B1") (pintype "bidirectional"))
      (node (ref "SW24") (pin "B2") (pinfunction "4_B2") (pintype "bidirectional"))
      (node (ref "SW36") (pin "B1") (pinfunction "3_B1") (pintype "bidirectional"))
      (node (ref "SW36") (pin "B2") (pinfunction "4_B2") (pintype "bidirectional"))
    )
    (net (code "29") (name "Net-(D16-C)") (class "Default")
      (node (ref "13") (pin "1") (pinfunction "1_1") (pintype "passive"))
      (node (ref "D16") (pin "K") (pinfunction "C_K") (pintype "passive"))
    )
    (net (code "30") (name "Net-(D17-C)") (class "Default")
      (node (ref "14") (pin "1") (pinfunction "1_1") (pintype "passive"))
      (node (ref "D17") (pin "K") (pinfunction "C_K") (pintype "passive"))
    )
    (net (code "31") (name "Net-(D18-C)") (class "Default")
      (node (ref "15") (pin "1") (pinfunction "1_1") (pintype "passive"))
      (node (ref "D18") (pin "K") (pinfunction "C_K") (pintype "passive"))
    )
    (net (code "32") (name "Net-(D19-C)") (class "Default")
      (node (ref "16") (pin "1") (pinfunction "1_1") (pintype "passive"))
      (node (ref "D19") (pin "K") (pinfunction "C_K") (pintype "passive"))
    )
    (net (code "33") (name "Net-(IC1-VIN)") (class "Default")
      (node (ref "C2") (pin "+") (pinfunction "+_+") (pintype "passive"))
      (node (ref "C4") (pin "2") (pinfunction "2_2") (pintype "passive"))
      (node (ref "IC1") (pin "3") (pinfunction "VIN_3") (pintype "input"))
      (node (ref "ONOFF") (pin "2") (pinfunction "P_2") (pintype "passive"))
    )
    (net (code "34") (name "Net-(IC3A-QA)") (class "Default")
      (node (ref "D12") (pin "A") (pinfunction "A_A") (pintype "passive"))
      (node (ref "IC3") (pin "15") (pinfunction "QA_15") (pintype "tri_state"))
    )
    (net (code "35") (name "Net-(IC3A-QB)") (class "Default")
      (node (ref "D13") (pin "A") (pinfunction "A_A") (pintype "passive"))
      (node (ref "IC3") (pin "1") (pinfunction "QB_1") (pintype "tri_state"))
    )
    (net (code "36") (name "Net-(IC3A-QC)") (class "Default")
      (node (ref "D14") (pin "A") (pinfunction "A_A") (pintype "passive"))
      (node (ref "IC3") (pin "2") (pinfunction "QC_2") (pintype "tri_state"))
    )
    (net (code "37") (name "Net-(IC3A-QD)") (class "Default")
      (node (ref "D15") (pin "A") (pinfunction "A_A") (pintype "passive"))
      (node (ref "IC3") (pin "3") (pinfunction "QD_3") (pintype "tri_state"))
    )
    (net (code "38") (name "Net-(IC3A-QE)") (class "Default")
      (node (ref "D16") (pin "A") (pinfunction "A_A") (pintype "passive"))
      (node (ref "IC3") (pin "4") (pinfunction "QE_4") (pintype "tri_state"))
    )
    (net (code "39") (name "Net-(IC3A-QF)") (class "Default")
      (node (ref "D17") (pin "A") (pinfunction "A_A") (pintype "passive"))
      (node (ref "IC3") (pin "5") (pinfunction "QF_5") (pintype "tri_state"))
    )
    (net (code "40") (name "Net-(IC3A-QG)") (class "Default")
      (node (ref "D18") (pin "A") (pinfunction "A_A") (pintype "passive"))
      (node (ref "IC3") (pin "6") (pinfunction "QG_6") (pintype "tri_state"))
    )
    (net (code "41") (name "Net-(IC3A-QH)") (class "Default")
      (node (ref "D19") (pin "A") (pinfunction "A_A") (pintype "passive"))
      (node (ref "IC3") (pin "7") (pinfunction "QH_7") (pintype "tri_state"))
    )
    (net (code "42") (name "Net-(IC3A-SER)") (class "Default")
      (node (ref "IC3") (pin "14") (pinfunction "SER_14") (pintype "input"))
      (node (ref "IC4") (pin "9") (pinfunction "QH*_9") (pintype "tri_state"))
    )
    (net (code "43") (name "Net-(IC4A-QA)") (class "Default")
      (node (ref "D4") (pin "A") (pinfunction "A_A") (pintype "passive"))
      (node (ref "IC4") (pin "15") (pinfunction "QA_15") (pintype "tri_state"))
    )
    (net (code "44") (name "Net-(IC4A-QB)") (class "Default")
      (node (ref "D5") (pin "A") (pinfunction "A_A") (pintype "passive"))
      (node (ref "IC4") (pin "1") (pinfunction "QB_1") (pintype "tri_state"))
    )
    (net (code "45") (name "Net-(IC4A-QC)") (class "Default")
      (node (ref "D6") (pin "A") (pinfunction "A_A") (pintype "passive"))
      (node (ref "IC4") (pin "2") (pinfunction "QC_2") (pintype "tri_state"))
    )
    (net (code "46") (name "Net-(IC4A-QD)") (class "Default")
      (node (ref "D7") (pin "A") (pinfunction "A_A") (pintype "passive"))
      (node (ref "IC4") (pin "3") (pinfunction "QD_3") (pintype "tri_state"))
    )
    (net (code "47") (name "Net-(IC4A-QE)") (class "Default")
      (node (ref "D8") (pin "A") (pinfunction "A_A") (pintype "passive"))
      (node (ref "IC4") (pin "4") (pinfunction "QE_4") (pintype "tri_state"))
    )
    (net (code "48") (name "Net-(IC4A-QF)") (class "Default")
      (node (ref "D9") (pin "A") (pinfunction "A_A") (pintype "passive"))
      (node (ref "IC4") (pin "5") (pinfunction "QF_5") (pintype "tri_state"))
    )
    (net (code "49") (name "Net-(IC4A-QG)") (class "Default")
      (node (ref "D10") (pin "A") (pinfunction "A_A") (pintype "passive"))
      (node (ref "IC4") (pin "6") (pinfunction "QG_6") (pintype "tri_state"))
    )
    (net (code "50") (name "Net-(IC4A-QH)") (class "Default")
      (node (ref "D11") (pin "A") (pinfunction "A_A") (pintype "passive"))
      (node (ref "IC4") (pin "7") (pinfunction "QH_7") (pintype "tri_state"))
    )
    (net (code "51") (name "Net-(MIDI-PadA)") (class "Default")
      (node (ref "MIDI") (pin "A") (pinfunction "A_A") (pintype "passive"))
      (node (ref "R5") (pin "1") (pinfunction "1_1") (pintype "passive"))
    )
    (net (code "52") (name "Net-(MIDI_OUT-Pad4)") (class "Default")
      (node (ref "MIDI_OUT") (pin "4") (pinfunction "4_4") (pintype "passive"))
      (node (ref "R1") (pin "2") (pinfunction "2_2") (pintype "passive"))
    )
    (net (code "53") (name "Net-(MIDI_OUT-Pad5)") (class "Default")
      (node (ref "MIDI_OUT") (pin "5") (pinfunction "5_5") (pintype "passive"))
      (node (ref "R2") (pin "1") (pinfunction "1_1") (pintype "passive"))
    )
    (net (code "54") (name "Net-(ONOFF-O)") (class "Default")
      (node (ref "D1") (pin "C") (pinfunction "C_C") (pintype "passive"))
      (node (ref "ONOFF") (pin "1") (pinfunction "O_1") (pintype "passive"))
    )
    (net (code "55") (name "Net-(PWR-PadA)") (class "Default")
      (node (ref "PWR") (pin "A") (pinfunction "A_A") (pintype "passive"))
      (node (ref "R4") (pin "2") (pinfunction "2_2") (pintype "passive"))
    )
    (net (code "56") (name "unconnected-(D1-PadA)") (class "Default")
      (node (ref "D1") (pin "A") (pinfunction "A_A") (pintype "passive"))
    )
    (net (code "57") (name "unconnected-(IC3A-QH*-Pad9)") (class "Default")
      (node (ref "IC3") (pin "9") (pinfunction "QH*_9") (pintype "tri_state"))
    )
    (net (code "58") (name "unconnected-(ICSP-Pad6)") (class "Default")
      (node (ref "ICSP") (pin "6") (pinfunction "6_6") (pintype "passive"))
    )
    (net (code "59") (name "unconnected-(MIDI_OUT-Pad1)") (class "Default")
      (node (ref "MIDI_OUT") (pin "1") (pinfunction "1_1") (pintype "passive"))
    )
    (net (code "60") (name "unconnected-(MIDI_OUT-Pad2)") (class "Default")
      (node (ref "MIDI_OUT") (pin "2") (pinfunction "2_2") (pintype "passive"))
    )
    (net (code "61") (name "unconnected-(MIDI_OUT-Pad3)") (class "Default")
      (node (ref "MIDI_OUT") (pin "3") (pinfunction "3_3") (pintype "passive"))
    )
    (net (code "62") (name "unconnected-(ONOFF-S-Pad3)") (class "Default")
      (node (ref "ONOFF") (pin "3") (pinfunction "S_3") (pintype "passive"))
    )
  )
)
